# main.net
KiCad netlist of a schematic drawn in EAGLE
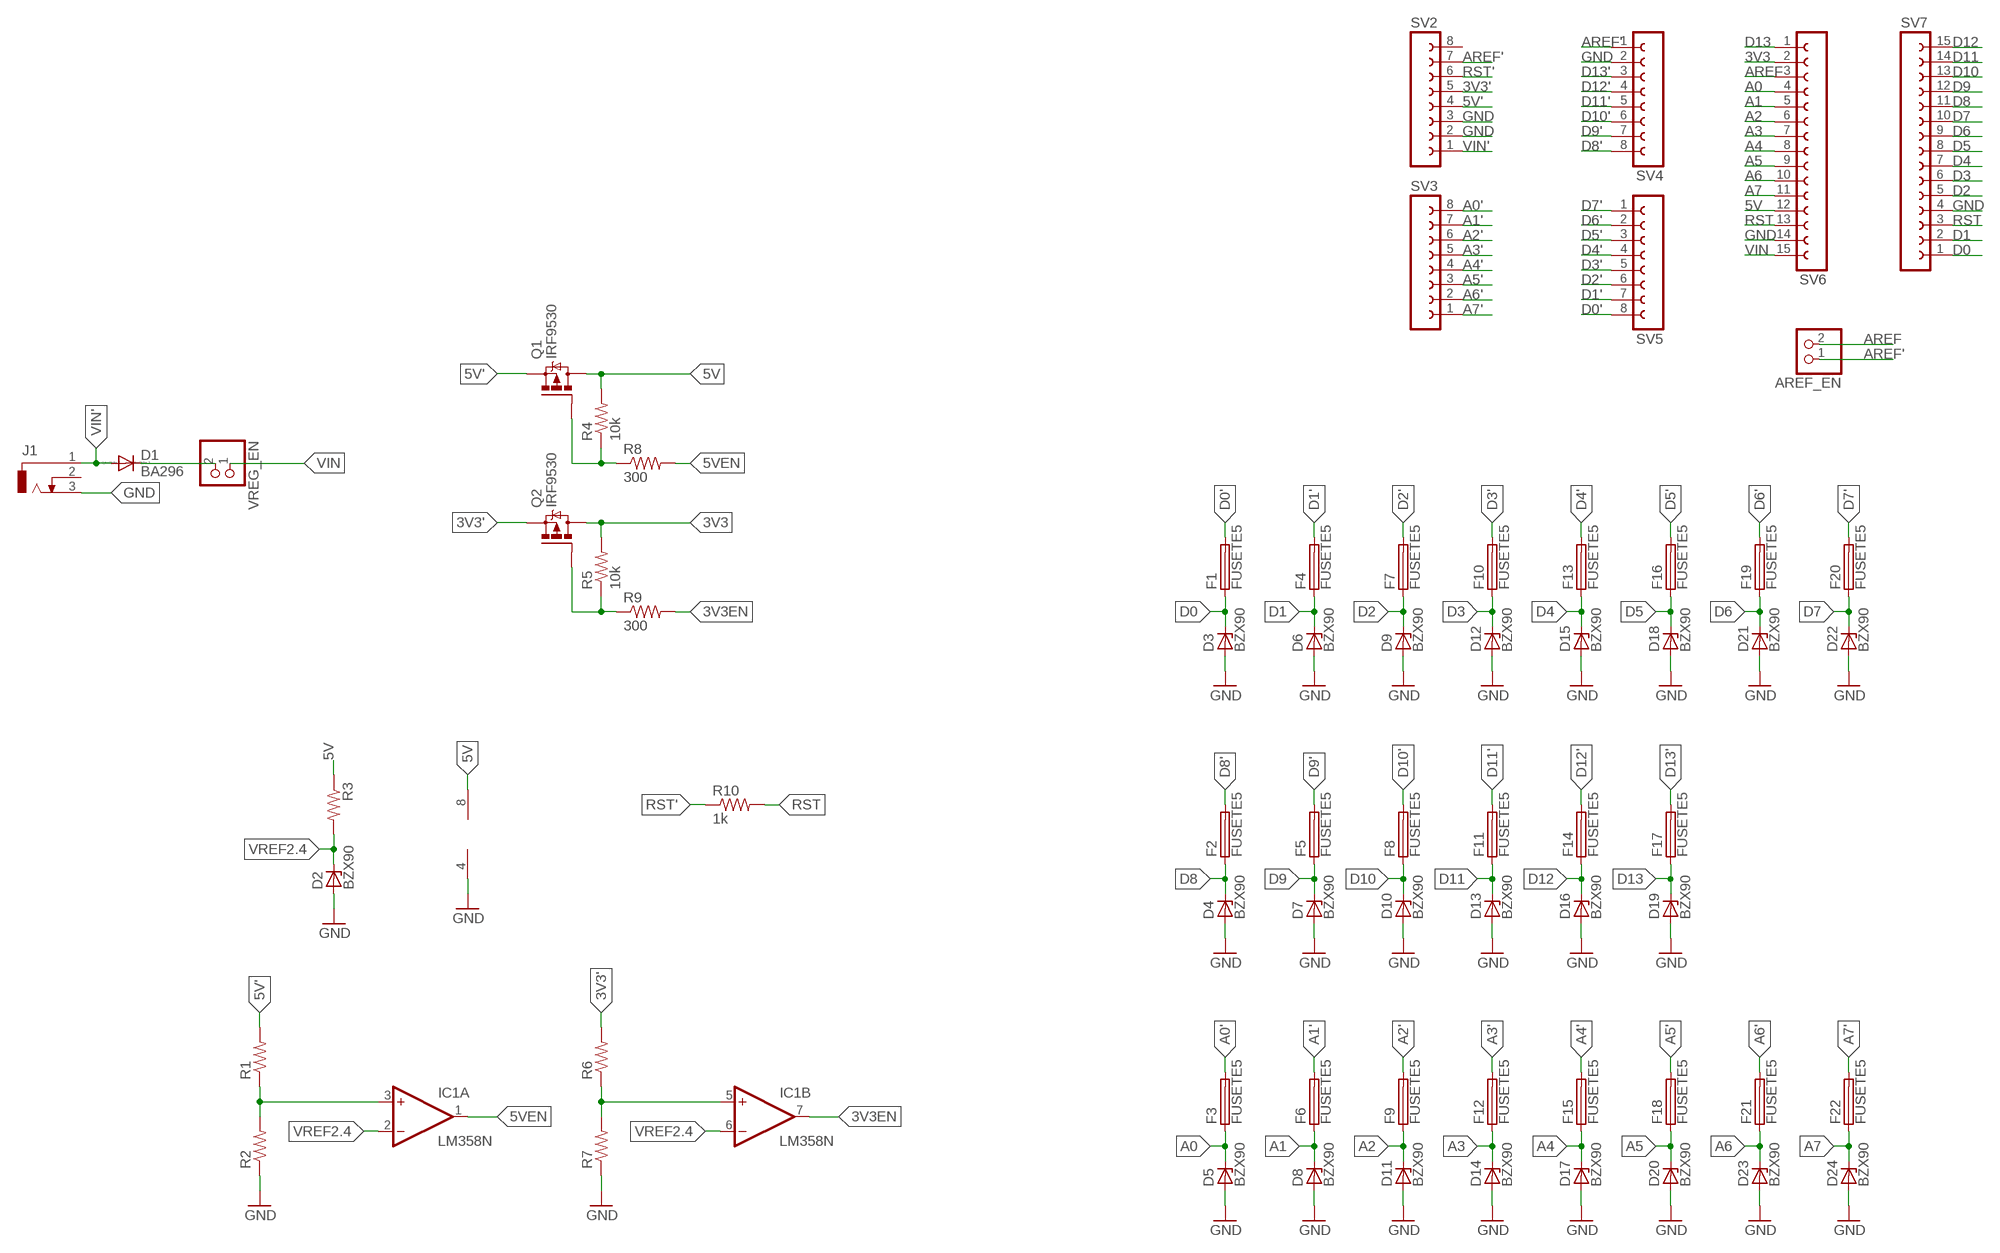
[diagram p0: schematic, sheet 1]

(export (version "E")
  (design (tool "Eeschema 10.0.6"))
  (components
    (comp (ref "AREF_EN")
      (value "PINHD-1X2")
      (footprint "eagle-import:1X02")
      (libsource (lib "eagle-import") (part "PINHD-1X2"))
    )
    (comp (ref "D1")
      (value "BA296")
      (footprint "eagle-import:P2-15")
      (libsource (lib "eagle-import") (part "BA296"))
    )
    (comp (ref "D2")
      (value "BZX90")
      (footprint "eagle-import:DO34Z7")
      (libsource (lib "eagle-import") (part "BZX90"))
    )
    (comp (ref "D3")
      (value "BZX90")
      (footprint "eagle-import:DO34Z7")
      (libsource (lib "eagle-import") (part "BZX90"))
    )
    (comp (ref "D4")
      (value "BZX90")
      (footprint "eagle-import:DO34Z7")
      (libsource (lib "eagle-import") (part "BZX90"))
    )
    (comp (ref "D5")
      (value "BZX90")
      (footprint "eagle-import:DO34Z7")
      (libsource (lib "eagle-import") (part "BZX90"))
    )
    (comp (ref "D6")
      (value "BZX90")
      (footprint "eagle-import:DO34Z7")
      (libsource (lib "eagle-import") (part "BZX90"))
    )
    (comp (ref "D7")
      (value "BZX90")
      (footprint "eagle-import:DO34Z7")
      (libsource (lib "eagle-import") (part "BZX90"))
    )
    (comp (ref "D8")
      (value "BZX90")
      (footprint "eagle-import:DO34Z7")
      (libsource (lib "eagle-import") (part "BZX90"))
    )
    (comp (ref "D9")
      (value "BZX90")
      (footprint "eagle-import:DO34Z7")
      (libsource (lib "eagle-import") (part "BZX90"))
    )
    (comp (ref "D10")
      (value "BZX90")
      (footprint "eagle-import:DO34Z7")
      (libsource (lib "eagle-import") (part "BZX90"))
    )
    (comp (ref "D11")
      (value "BZX90")
      (footprint "eagle-import:DO34Z7")
      (libsource (lib "eagle-import") (part "BZX90"))
    )
    (comp (ref "D12")
      (value "BZX90")
      (footprint "eagle-import:DO34Z7")
      (libsource (lib "eagle-import") (part "BZX90"))
    )
    (comp (ref "D13")
      (value "BZX90")
      (footprint "eagle-import:DO34Z7")
      (libsource (lib "eagle-import") (part "BZX90"))
    )
    (comp (ref "D14")
      (value "BZX90")
      (footprint "eagle-import:DO34Z7")
      (libsource (lib "eagle-import") (part "BZX90"))
    )
    (comp (ref "D15")
      (value "BZX90")
      (footprint "eagle-import:DO34Z7")
      (libsource (lib "eagle-import") (part "BZX90"))
    )
    (comp (ref "D16")
      (value "BZX90")
      (footprint "eagle-import:DO34Z7")
      (libsource (lib "eagle-import") (part "BZX90"))
    )
    (comp (ref "D17")
      (value "BZX90")
      (footprint "eagle-import:DO34Z7")
      (libsource (lib "eagle-import") (part "BZX90"))
    )
    (comp (ref "D18")
      (value "BZX90")
      (footprint "eagle-import:DO34Z7")
      (libsource (lib "eagle-import") (part "BZX90"))
    )
    (comp (ref "D19")
      (value "BZX90")
      (footprint "eagle-import:DO34Z7")
      (libsource (lib "eagle-import") (part "BZX90"))
    )
    (comp (ref "D20")
      (value "BZX90")
      (footprint "eagle-import:DO34Z7")
      (libsource (lib "eagle-import") (part "BZX90"))
    )
    (comp (ref "D21")
      (value "BZX90")
      (footprint "eagle-import:DO34Z7")
      (libsource (lib "eagle-import") (part "BZX90"))
    )
    (comp (ref "D22")
      (value "BZX90")
      (footprint "eagle-import:DO34Z7")
      (libsource (lib "eagle-import") (part "BZX90"))
    )
    (comp (ref "D23")
      (value "BZX90")
      (footprint "eagle-import:DO34Z7")
      (libsource (lib "eagle-import") (part "BZX90"))
    )
    (comp (ref "D24")
      (value "BZX90")
      (footprint "eagle-import:DO34Z7")
      (libsource (lib "eagle-import") (part "BZX90"))
    )
    (comp (ref "F1")
      (value "FUSETE5")
      (footprint "eagle-import:TE5")
      (libsource (lib "eagle-import") (part "FUSETE5"))
    )
    (comp (ref "F2")
      (value "FUSETE5")
      (footprint "eagle-import:TE5")
      (libsource (lib "eagle-import") (part "FUSETE5"))
    )
    (comp (ref "F3")
      (value "FUSETE5")
      (footprint "eagle-import:TE5")
      (libsource (lib "eagle-import") (part "FUSETE5"))
    )
    (comp (ref "F4")
      (value "FUSETE5")
      (footprint "eagle-import:TE5")
      (libsource (lib "eagle-import") (part "FUSETE5"))
    )
    (comp (ref "F5")
      (value "FUSETE5")
      (footprint "eagle-import:TE5")
      (libsource (lib "eagle-import") (part "FUSETE5"))
    )
    (comp (ref "F6")
      (value "FUSETE5")
      (footprint "eagle-import:TE5")
      (libsource (lib "eagle-import") (part "FUSETE5"))
    )
    (comp (ref "F7")
      (value "FUSETE5")
      (footprint "eagle-import:TE5")
      (libsource (lib "eagle-import") (part "FUSETE5"))
    )
    (comp (ref "F8")
      (value "FUSETE5")
      (footprint "eagle-import:TE5")
      (libsource (lib "eagle-import") (part "FUSETE5"))
    )
    (comp (ref "F9")
      (value "FUSETE5")
      (footprint "eagle-import:TE5")
      (libsource (lib "eagle-import") (part "FUSETE5"))
    )
    (comp (ref "F10")
      (value "FUSETE5")
      (footprint "eagle-import:TE5")
      (libsource (lib "eagle-import") (part "FUSETE5"))
    )
    (comp (ref "F11")
      (value "FUSETE5")
      (footprint "eagle-import:TE5")
      (libsource (lib "eagle-import") (part "FUSETE5"))
    )
    (comp (ref "F12")
      (value "FUSETE5")
      (footprint "eagle-import:TE5")
      (libsource (lib "eagle-import") (part "FUSETE5"))
    )
    (comp (ref "F13")
      (value "FUSETE5")
      (footprint "eagle-import:TE5")
      (libsource (lib "eagle-import") (part "FUSETE5"))
    )
    (comp (ref "F14")
      (value "FUSETE5")
      (footprint "eagle-import:TE5")
      (libsource (lib "eagle-import") (part "FUSETE5"))
    )
    (comp (ref "F15")
      (value "FUSETE5")
      (footprint "eagle-import:TE5")
      (libsource (lib "eagle-import") (part "FUSETE5"))
    )
    (comp (ref "F16")
      (value "FUSETE5")
      (footprint "eagle-import:TE5")
      (libsource (lib "eagle-import") (part "FUSETE5"))
    )
    (comp (ref "F17")
      (value "FUSETE5")
      (footprint "eagle-import:TE5")
      (libsource (lib "eagle-import") (part "FUSETE5"))
    )
    (comp (ref "F18")
      (value "FUSETE5")
      (footprint "eagle-import:TE5")
      (libsource (lib "eagle-import") (part "FUSETE5"))
    )
    (comp (ref "F19")
      (value "FUSETE5")
      (footprint "eagle-import:TE5")
      (libsource (lib "eagle-import") (part "FUSETE5"))
    )
    (comp (ref "F20")
      (value "FUSETE5")
      (footprint "eagle-import:TE5")
      (libsource (lib "eagle-import") (part "FUSETE5"))
    )
    (comp (ref "F21")
      (value "FUSETE5")
      (footprint "eagle-import:TE5")
      (libsource (lib "eagle-import") (part "FUSETE5"))
    )
    (comp (ref "F22")
      (value "FUSETE5")
      (footprint "eagle-import:TE5")
      (libsource (lib "eagle-import") (part "FUSETE5"))
    )
    (comp (ref "IC1")
      (value "LM358N")
      (footprint "eagle-import:DIL08")
      (libsource (lib "eagle-import") (part "LM358N"))
    )
    (comp (ref "J1")
      (value "DCJ0303")
      (footprint "eagle-import:DCJ0303")
      (libsource (lib "eagle-import") (part "DCJ0303"))
    )
    (comp (ref "Q1")
      (value "IRF9530")
      (footprint "eagle-import:TO220BV")
      (libsource (lib "eagle-import") (part "IRF9530"))
    )
    (comp (ref "Q2")
      (value "IRF9530")
      (footprint "eagle-import:TO220BV")
      (libsource (lib "eagle-import") (part "IRF9530"))
    )
    (comp (ref "R1")
      (value "R-US_0204/7")
      (footprint "eagle-import:0204_7")
      (libsource (lib "eagle-import") (part "R-US_0204/7"))
    )
    (comp (ref "R2")
      (value "R-US_0204/7")
      (footprint "eagle-import:0204_7")
      (libsource (lib "eagle-import") (part "R-US_0204/7"))
    )
    (comp (ref "R3")
      (value "R-US_0204/7")
      (footprint "eagle-import:0204_7")
      (libsource (lib "eagle-import") (part "R-US_0204/7"))
    )
    (comp (ref "R4")
      (value "10k")
      (footprint "eagle-import:0204_7")
      (libsource (lib "eagle-import") (part "R-US_0204/7"))
    )
    (comp (ref "R5")
      (value "10k")
      (footprint "eagle-import:0204_7")
      (libsource (lib "eagle-import") (part "R-US_0204/7"))
    )
    (comp (ref "R6")
      (value "R-US_0204/7")
      (footprint "eagle-import:0204_7")
      (libsource (lib "eagle-import") (part "R-US_0204/7"))
    )
    (comp (ref "R7")
      (value "R-US_0204/7")
      (footprint "eagle-import:0204_7")
      (libsource (lib "eagle-import") (part "R-US_0204/7"))
    )
    (comp (ref "R8")
      (value "300")
      (footprint "eagle-import:0204_7")
      (libsource (lib "eagle-import") (part "R-US_0204/7"))
    )
    (comp (ref "R9")
      (value "300")
      (footprint "eagle-import:0204_7")
      (libsource (lib "eagle-import") (part "R-US_0204/7"))
    )
    (comp (ref "R10")
      (value "1k")
      (footprint "eagle-import:0204_7")
      (libsource (lib "eagle-import") (part "R-US_0204/7"))
    )
    (comp (ref "SV2")
      (value "FE08-1")
      (footprint "eagle-import:FE08")
      (libsource (lib "eagle-import") (part "FE08-1"))
    )
    (comp (ref "SV3")
      (value "FE08-1")
      (footprint "eagle-import:FE08")
      (libsource (lib "eagle-import") (part "FE08-1"))
    )
    (comp (ref "SV4")
      (value "FE08-1")
      (footprint "eagle-import:FE08")
      (libsource (lib "eagle-import") (part "FE08-1"))
    )
    (comp (ref "SV5")
      (value "FE08-1")
      (footprint "eagle-import:FE08")
      (libsource (lib "eagle-import") (part "FE08-1"))
    )
    (comp (ref "SV6")
      (value "FE15-1")
      (footprint "eagle-import:FE15")
      (libsource (lib "eagle-import") (part "FE15-1"))
    )
    (comp (ref "SV7")
      (value "FE15-1")
      (footprint "eagle-import:FE15")
      (libsource (lib "eagle-import") (part "FE15-1"))
    )
    (comp (ref "VREG_EN")
      (value "PINHD-1X2")
      (footprint "eagle-import:1X02")
      (libsource (lib "eagle-import") (part "PINHD-1X2"))
    )
  )
  (nets
    (net (code "1") (name "/AREF") (class "Default")
      (node (ref "AREF_EN") (pin "2") (pinfunction "2_2") (pintype "passive"))
      (node (ref "SV6") (pin "3") (pinfunction "3_3") (pintype "passive"))
    )
    (net (code "2") (name "/AREF'") (class "Default")
      (node (ref "AREF_EN") (pin "1") (pinfunction "1_1") (pintype "passive"))
      (node (ref "SV2") (pin "7") (pinfunction "7_7") (pintype "passive"))
      (node (ref "SV4") (pin "1") (pinfunction "1_1") (pintype "passive"))
    )
    (net (code "3") (name "3V3") (class "Default")
      (node (ref "Q2") (pin "D") (pinfunction "D_D") (pintype "passive"))
      (node (ref "R5") (pin "2") (pinfunction "2_2") (pintype "passive"))
      (node (ref "SV6") (pin "2") (pinfunction "2_2") (pintype "passive"))
    )
    (net (code "4") (name "3V3'") (class "Default")
      (node (ref "Q2") (pin "S") (pinfunction "S_S") (pintype "passive"))
      (node (ref "R6") (pin "2") (pinfunction "2_2") (pintype "passive"))
      (node (ref "SV2") (pin "5") (pinfunction "5_5") (pintype "passive"))
    )
    (net (code "5") (name "3V3EN") (class "Default")
      (node (ref "IC1") (pin "7") (pinfunction "OUT_7") (pintype "output"))
      (node (ref "R9") (pin "2") (pinfunction "2_2") (pintype "passive"))
    )
    (net (code "6") (name "5V") (class "Default")
      (node (ref "IC1") (pin "8") (pinfunction "V+_8") (pintype "power_in"))
      (node (ref "Q1") (pin "D") (pinfunction "D_D") (pintype "passive"))
      (node (ref "R3") (pin "1") (pinfunction "1_1") (pintype "passive"))
      (node (ref "R4") (pin "2") (pinfunction "2_2") (pintype "passive"))
      (node (ref "SV6") (pin "12") (pinfunction "12_12") (pintype "passive"))
    )
    (net (code "7") (name "5V'") (class "Default")
      (node (ref "Q1") (pin "S") (pinfunction "S_S") (pintype "passive"))
      (node (ref "R1") (pin "2") (pinfunction "2_2") (pintype "passive"))
      (node (ref "SV2") (pin "4") (pinfunction "4_4") (pintype "passive"))
    )
    (net (code "8") (name "5VEN") (class "Default")
      (node (ref "IC1") (pin "1") (pinfunction "OUT_1") (pintype "output"))
      (node (ref "R8") (pin "2") (pinfunction "2_2") (pintype "passive"))
    )
    (net (code "9") (name "A0") (class "Default")
      (node (ref "D5") (pin "C") (pinfunction "C_C") (pintype "passive"))
      (node (ref "F3") (pin "1") (pinfunction "1_1") (pintype "passive"))
      (node (ref "SV6") (pin "4") (pinfunction "4_4") (pintype "passive"))
    )
    (net (code "10") (name "A0'") (class "Default")
      (node (ref "F3") (pin "2") (pinfunction "2_2") (pintype "passive"))
      (node (ref "SV3") (pin "8") (pinfunction "8_8") (pintype "passive"))
    )
    (net (code "11") (name "A1") (class "Default")
      (node (ref "D8") (pin "C") (pinfunction "C_C") (pintype "passive"))
      (node (ref "F6") (pin "1") (pinfunction "1_1") (pintype "passive"))
      (node (ref "SV6") (pin "5") (pinfunction "5_5") (pintype "passive"))
    )
    (net (code "12") (name "A1'") (class "Default")
      (node (ref "F6") (pin "2") (pinfunction "2_2") (pintype "passive"))
      (node (ref "SV3") (pin "7") (pinfunction "7_7") (pintype "passive"))
    )
    (net (code "13") (name "A2") (class "Default")
      (node (ref "D11") (pin "C") (pinfunction "C_C") (pintype "passive"))
      (node (ref "F9") (pin "1") (pinfunction "1_1") (pintype "passive"))
      (node (ref "SV6") (pin "6") (pinfunction "6_6") (pintype "passive"))
    )
    (net (code "14") (name "A2'") (class "Default")
      (node (ref "F9") (pin "2") (pinfunction "2_2") (pintype "passive"))
      (node (ref "SV3") (pin "6") (pinfunction "6_6") (pintype "passive"))
    )
    (net (code "15") (name "A3") (class "Default")
      (node (ref "D14") (pin "C") (pinfunction "C_C") (pintype "passive"))
      (node (ref "F12") (pin "1") (pinfunction "1_1") (pintype "passive"))
      (node (ref "SV6") (pin "7") (pinfunction "7_7") (pintype "passive"))
    )
    (net (code "16") (name "A3'") (class "Default")
      (node (ref "F12") (pin "2") (pinfunction "2_2") (pintype "passive"))
      (node (ref "SV3") (pin "5") (pinfunction "5_5") (pintype "passive"))
    )
    (net (code "17") (name "A4") (class "Default")
      (node (ref "D17") (pin "C") (pinfunction "C_C") (pintype "passive"))
      (node (ref "F15") (pin "1") (pinfunction "1_1") (pintype "passive"))
      (node (ref "SV6") (pin "8") (pinfunction "8_8") (pintype "passive"))
    )
    (net (code "18") (name "A4'") (class "Default")
      (node (ref "F15") (pin "2") (pinfunction "2_2") (pintype "passive"))
      (node (ref "SV3") (pin "4") (pinfunction "4_4") (pintype "passive"))
    )
    (net (code "19") (name "A5") (class "Default")
      (node (ref "D20") (pin "C") (pinfunction "C_C") (pintype "passive"))
      (node (ref "F18") (pin "1") (pinfunction "1_1") (pintype "passive"))
      (node (ref "SV6") (pin "9") (pinfunction "9_9") (pintype "passive"))
    )
    (net (code "20") (name "A5'") (class "Default")
      (node (ref "F18") (pin "2") (pinfunction "2_2") (pintype "passive"))
      (node (ref "SV3") (pin "3") (pinfunction "3_3") (pintype "passive"))
    )
    (net (code "21") (name "A6") (class "Default")
      (node (ref "D23") (pin "C") (pinfunction "C_C") (pintype "passive"))
      (node (ref "F21") (pin "1") (pinfunction "1_1") (pintype "passive"))
      (node (ref "SV6") (pin "10") (pinfunction "10_10") (pintype "passive"))
    )
    (net (code "22") (name "A6'") (class "Default")
      (node (ref "F21") (pin "2") (pinfunction "2_2") (pintype "passive"))
      (node (ref "SV3") (pin "2") (pinfunction "2_2") (pintype "passive"))
    )
    (net (code "23") (name "A7") (class "Default")
      (node (ref "D24") (pin "C") (pinfunction "C_C") (pintype "passive"))
      (node (ref "F22") (pin "1") (pinfunction "1_1") (pintype "passive"))
      (node (ref "SV6") (pin "11") (pinfunction "11_11") (pintype "passive"))
    )
    (net (code "24") (name "A7'") (class "Default")
      (node (ref "F22") (pin "2") (pinfunction "2_2") (pintype "passive"))
      (node (ref "SV3") (pin "1") (pinfunction "1_1") (pintype "passive"))
    )
    (net (code "25") (name "D0") (class "Default")
      (node (ref "D3") (pin "C") (pinfunction "C_C") (pintype "passive"))
      (node (ref "F1") (pin "1") (pinfunction "1_1") (pintype "passive"))
      (node (ref "SV7") (pin "1") (pinfunction "1_1") (pintype "passive"))
    )
    (net (code "26") (name "D0'") (class "Default")
      (node (ref "F1") (pin "2") (pinfunction "2_2") (pintype "passive"))
      (node (ref "SV5") (pin "8") (pinfunction "8_8") (pintype "passive"))
    )
    (net (code "27") (name "D1") (class "Default")
      (node (ref "D6") (pin "C") (pinfunction "C_C") (pintype "passive"))
      (node (ref "F4") (pin "1") (pinfunction "1_1") (pintype "passive"))
      (node (ref "SV7") (pin "2") (pinfunction "2_2") (pintype "passive"))
    )
    (net (code "28") (name "D1'") (class "Default")
      (node (ref "F4") (pin "2") (pinfunction "2_2") (pintype "passive"))
      (node (ref "SV5") (pin "7") (pinfunction "7_7") (pintype "passive"))
    )
    (net (code "29") (name "D2") (class "Default")
      (node (ref "D9") (pin "C") (pinfunction "C_C") (pintype "passive"))
      (node (ref "F7") (pin "1") (pinfunction "1_1") (pintype "passive"))
      (node (ref "SV7") (pin "5") (pinfunction "5_5") (pintype "passive"))
    )
    (net (code "30") (name "D2'") (class "Default")
      (node (ref "F7") (pin "2") (pinfunction "2_2") (pintype "passive"))
      (node (ref "SV5") (pin "6") (pinfunction "6_6") (pintype "passive"))
    )
    (net (code "31") (name "D3") (class "Default")
      (node (ref "D12") (pin "C") (pinfunction "C_C") (pintype "passive"))
      (node (ref "F10") (pin "1") (pinfunction "1_1") (pintype "passive"))
      (node (ref "SV7") (pin "6") (pinfunction "6_6") (pintype "passive"))
    )
    (net (code "32") (name "D3'") (class "Default")
      (node (ref "F10") (pin "2") (pinfunction "2_2") (pintype "passive"))
      (node (ref "SV5") (pin "5") (pinfunction "5_5") (pintype "passive"))
    )
    (net (code "33") (name "D4") (class "Default")
      (node (ref "D15") (pin "C") (pinfunction "C_C") (pintype "passive"))
      (node (ref "F13") (pin "1") (pinfunction "1_1") (pintype "passive"))
      (node (ref "SV7") (pin "7") (pinfunction "7_7") (pintype "passive"))
    )
    (net (code "34") (name "D4'") (class "Default")
      (node (ref "F13") (pin "2") (pinfunction "2_2") (pintype "passive"))
      (node (ref "SV5") (pin "4") (pinfunction "4_4") (pintype "passive"))
    )
    (net (code "35") (name "D5") (class "Default")
      (node (ref "D18") (pin "C") (pinfunction "C_C") (pintype "passive"))
      (node (ref "F16") (pin "1") (pinfunction "1_1") (pintype "passive"))
      (node (ref "SV7") (pin "8") (pinfunction "8_8") (pintype "passive"))
    )
    (net (code "36") (name "D5'") (class "Default")
      (node (ref "F16") (pin "2") (pinfunction "2_2") (pintype "passive"))
      (node (ref "SV5") (pin "3") (pinfunction "3_3") (pintype "passive"))
    )
    (net (code "37") (name "D6") (class "Default")
      (node (ref "D21") (pin "C") (pinfunction "C_C") (pintype "passive"))
      (node (ref "F19") (pin "1") (pinfunction "1_1") (pintype "passive"))
      (node (ref "SV7") (pin "9") (pinfunction "9_9") (pintype "passive"))
    )
    (net (code "38") (name "D6'") (class "Default")
      (node (ref "F19") (pin "2") (pinfunction "2_2") (pintype "passive"))
      (node (ref "SV5") (pin "2") (pinfunction "2_2") (pintype "passive"))
    )
    (net (code "39") (name "D7") (class "Default")
      (node (ref "D22") (pin "C") (pinfunction "C_C") (pintype "passive"))
      (node (ref "F20") (pin "1") (pinfunction "1_1") (pintype "passive"))
      (node (ref "SV7") (pin "10") (pinfunction "10_10") (pintype "passive"))
    )
    (net (code "40") (name "D7'") (class "Default")
      (node (ref "F20") (pin "2") (pinfunction "2_2") (pintype "passive"))
      (node (ref "SV5") (pin "1") (pinfunction "1_1") (pintype "passive"))
    )
    (net (code "41") (name "D8") (class "Default")
      (node (ref "D4") (pin "C") (pinfunction "C_C") (pintype "passive"))
      (node (ref "F2") (pin "1") (pinfunction "1_1") (pintype "passive"))
      (node (ref "SV7") (pin "11") (pinfunction "11_11") (pintype "passive"))
    )
    (net (code "42") (name "D8'") (class "Default")
      (node (ref "F2") (pin "2") (pinfunction "2_2") (pintype "passive"))
      (node (ref "SV4") (pin "8") (pinfunction "8_8") (pintype "passive"))
    )
    (net (code "43") (name "D9") (class "Default")
      (node (ref "D7") (pin "C") (pinfunction "C_C") (pintype "passive"))
      (node (ref "F5") (pin "1") (pinfunction "1_1") (pintype "passive"))
      (node (ref "SV7") (pin "12") (pinfunction "12_12") (pintype "passive"))
    )
    (net (code "44") (name "D9'") (class "Default")
      (node (ref "F5") (pin "2") (pinfunction "2_2") (pintype "passive"))
      (node (ref "SV4") (pin "7") (pinfunction "7_7") (pintype "passive"))
    )
    (net (code "45") (name "D10") (class "Default")
      (node (ref "D10") (pin "C") (pinfunction "C_C") (pintype "passive"))
      (node (ref "F8") (pin "1") (pinfunction "1_1") (pintype "passive"))
      (node (ref "SV7") (pin "13") (pinfunction "13_13") (pintype "passive"))
    )
    (net (code "46") (name "D10'") (class "Default")
      (node (ref "F8") (pin "2") (pinfunction "2_2") (pintype "passive"))
      (node (ref "SV4") (pin "6") (pinfunction "6_6") (pintype "passive"))
    )
    (net (code "47") (name "D11") (class "Default")
      (node (ref "D13") (pin "C") (pinfunction "C_C") (pintype "passive"))
      (node (ref "F11") (pin "1") (pinfunction "1_1") (pintype "passive"))
      (node (ref "SV7") (pin "14") (pinfunction "14_14") (pintype "passive"))
    )
    (net (code "48") (name "D11'") (class "Default")
      (node (ref "F11") (pin "2") (pinfunction "2_2") (pintype "passive"))
      (node (ref "SV4") (pin "5") (pinfunction "5_5") (pintype "passive"))
    )
    (net (code "49") (name "D12") (class "Default")
      (node (ref "D16") (pin "C") (pinfunction "C_C") (pintype "passive"))
      (node (ref "F14") (pin "1") (pinfunction "1_1") (pintype "passive"))
      (node (ref "SV7") (pin "15") (pinfunction "15_15") (pintype "passive"))
    )
    (net (code "50") (name "D12'") (class "Default")
      (node (ref "F14") (pin "2") (pinfunction "2_2") (pintype "passive"))
      (node (ref "SV4") (pin "4") (pinfunction "4_4") (pintype "passive"))
    )
    (net (code "51") (name "D13") (class "Default")
      (node (ref "D19") (pin "C") (pinfunction "C_C") (pintype "passive"))
      (node (ref "F17") (pin "1") (pinfunction "1_1") (pintype "passive"))
      (node (ref "SV6") (pin "1") (pinfunction "1_1") (pintype "passive"))
    )
    (net (code "52") (name "D13'") (class "Default")
      (node (ref "F17") (pin "2") (pinfunction "2_2") (pintype "passive"))
      (node (ref "SV4") (pin "3") (pinfunction "3_3") (pintype "passive"))
    )
    (net (code "53") (name "GND") (class "Default")
      (node (ref "D10") (pin "A") (pinfunction "A_A") (pintype "passive"))
      (node (ref "D11") (pin "A") (pinfunction "A_A") (pintype "passive"))
      (node (ref "D12") (pin "A") (pinfunction "A_A") (pintype "passive"))
      (node (ref "D13") (pin "A") (pinfunction "A_A") (pintype "passive"))
      (node (ref "D14") (pin "A") (pinfunction "A_A") (pintype "passive"))
      (node (ref "D15") (pin "A") (pinfunction "A_A") (pintype "passive"))
      (node (ref "D16") (pin "A") (pinfunction "A_A") (pintype "passive"))
      (node (ref "D17") (pin "A") (pinfunction "A_A") (pintype "passive"))
      (node (ref "D18") (pin "A") (pinfunction "A_A") (pintype "passive"))
      (node (ref "D19") (pin "A") (pinfunction "A_A") (pintype "passive"))
      (node (ref "D2") (pin "A") (pinfunction "A_A") (pintype "passive"))
      (node (ref "D20") (pin "A") (pinfunction "A_A") (pintype "passive"))
      (node (ref "D21") (pin "A") (pinfunction "A_A") (pintype "passive"))
      (node (ref "D22") (pin "A") (pinfunction "A_A") (pintype "passive"))
      (node (ref "D23") (pin "A") (pinfunction "A_A") (pintype "passive"))
      (node (ref "D24") (pin "A") (pinfunction "A_A") (pintype "passive"))
      (node (ref "D3") (pin "A") (pinfunction "A_A") (pintype "passive"))
      (node (ref "D4") (pin "A") (pinfunction "A_A") (pintype "passive"))
      (node (ref "D5") (pin "A") (pinfunction "A_A") (pintype "passive"))
      (node (ref "D6") (pin "A") (pinfunction "A_A") (pintype "passive"))
      (node (ref "D7") (pin "A") (pinfunction "A_A") (pintype "passive"))
      (node (ref "D8") (pin "A") (pinfunction "A_A") (pintype "passive"))
      (node (ref "D9") (pin "A") (pinfunction "A_A") (pintype "passive"))
      (node (ref "IC1") (pin "4") (pinfunction "V-_4") (pintype "power_in"))
      (node (ref "J1") (pin "3") (pinfunction "3_3") (pintype "passive"))
      (node (ref "R2") (pin "1") (pinfunction "1_1") (pintype "passive"))
      (node (ref "R7") (pin "1") (pinfunction "1_1") (pintype "passive"))
      (node (ref "SV2") (pin "2") (pinfunction "2_2") (pintype "passive"))
      (node (ref "SV2") (pin "3") (pinfunction "3_3") (pintype "passive"))
      (node (ref "SV4") (pin "2") (pinfunction "2_2") (pintype "passive"))
      (node (ref "SV6") (pin "14") (pinfunction "14_14") (pintype "passive"))
      (node (ref "SV7") (pin "4") (pinfunction "4_4") (pintype "passive"))
    )
    (net (code "54") (name "Net-(D1-PadC)") (class "Default")
      (node (ref "D1") (pin "C") (pinfunction "C_C") (pintype "passive"))
      (node (ref "VREG_EN") (pin "2") (pinfunction "2_2") (pintype "passive"))
    )
    (net (code "55") (name "Net-(IC1A-+IN)") (class "Default")
      (node (ref "IC1") (pin "3") (pinfunction "+IN_3") (pintype "input"))
      (node (ref "R1") (pin "1") (pinfunction "1_1") (pintype "passive"))
      (node (ref "R2") (pin "2") (pinfunction "2_2") (pintype "passive"))
    )
    (net (code "56") (name "Net-(IC1B-+IN)") (class "Default")
      (node (ref "IC1") (pin "5") (pinfunction "+IN_5") (pintype "input"))
      (node (ref "R6") (pin "1") (pinfunction "1_1") (pintype "passive"))
      (node (ref "R7") (pin "2") (pinfunction "2_2") (pintype "passive"))
    )
    (net (code "57") (name "Net-(Q1-PadG)") (class "Default")
      (node (ref "Q1") (pin "G") (pinfunction "G_G") (pintype "passive"))
      (node (ref "R4") (pin "1") (pinfunction "1_1") (pintype "passive"))
      (node (ref "R8") (pin "1") (pinfunction "1_1") (pintype "passive"))
    )
    (net (code "58") (name "Net-(Q2-PadG)") (class "Default")
      (node (ref "Q2") (pin "G") (pinfunction "G_G") (pintype "passive"))
      (node (ref "R5") (pin "1") (pinfunction "1_1") (pintype "passive"))
      (node (ref "R9") (pin "1") (pinfunction "1_1") (pintype "passive"))
    )
    (net (code "59") (name "RST") (class "Default")
      (node (ref "R10") (pin "2") (pinfunction "2_2") (pintype "passive"))
      (node (ref "SV6") (pin "13") (pinfunction "13_13") (pintype "passive"))
      (node (ref "SV7") (pin "3") (pinfunction "3_3") (pintype "passive"))
    )
    (net (code "60") (name "RST'") (class "Default")
      (node (ref "R10") (pin "1") (pinfunction "1_1") (pintype "passive"))
      (node (ref "SV2") (pin "6") (pinfunction "6_6") (pintype "passive"))
    )
    (net (code "61") (name "VIN") (class "Default")
      (node (ref "SV6") (pin "15") (pinfunction "15_15") (pintype "passive"))
      (node (ref "VREG_EN") (pin "1") (pinfunction "1_1") (pintype "passive"))
    )
    (net (code "62") (name "VIN'") (class "Default")
      (node (ref "D1") (pin "A") (pinfunction "A_A") (pintype "passive"))
      (node (ref "J1") (pin "1") (pinfunction "1_1") (pintype "passive"))
      (node (ref "SV2") (pin "1") (pinfunction "1_1") (pintype "passive"))
    )
    (net (code "63") (name "VREF2.4") (class "Default")
      (node (ref "D2") (pin "C") (pinfunction "C_C") (pintype "passive"))
      (node (ref "IC1") (pin "2") (pinfunction "-IN_2") (pintype "input"))
      (node (ref "IC1") (pin "6") (pinfunction "-IN_6") (pintype "input"))
      (node (ref "R3") (pin "2") (pinfunction "2_2") (pintype "passive"))
    )
    (net (code "64") (name "unconnected-(J1-Pad2)") (class "Default")
      (node (ref "J1") (pin "2") (pinfunction "2_2") (pintype "passive"))
    )
    (net (code "65") (name "unconnected-(SV2-Pad8)") (class "Default")
      (node (ref "SV2") (pin "8") (pinfunction "8_8") (pintype "passive"))
    )
  )
)
